# 02_-_EnergyManagementUnit.net
KiCad netlist of a schematic drawn in Altium Designer
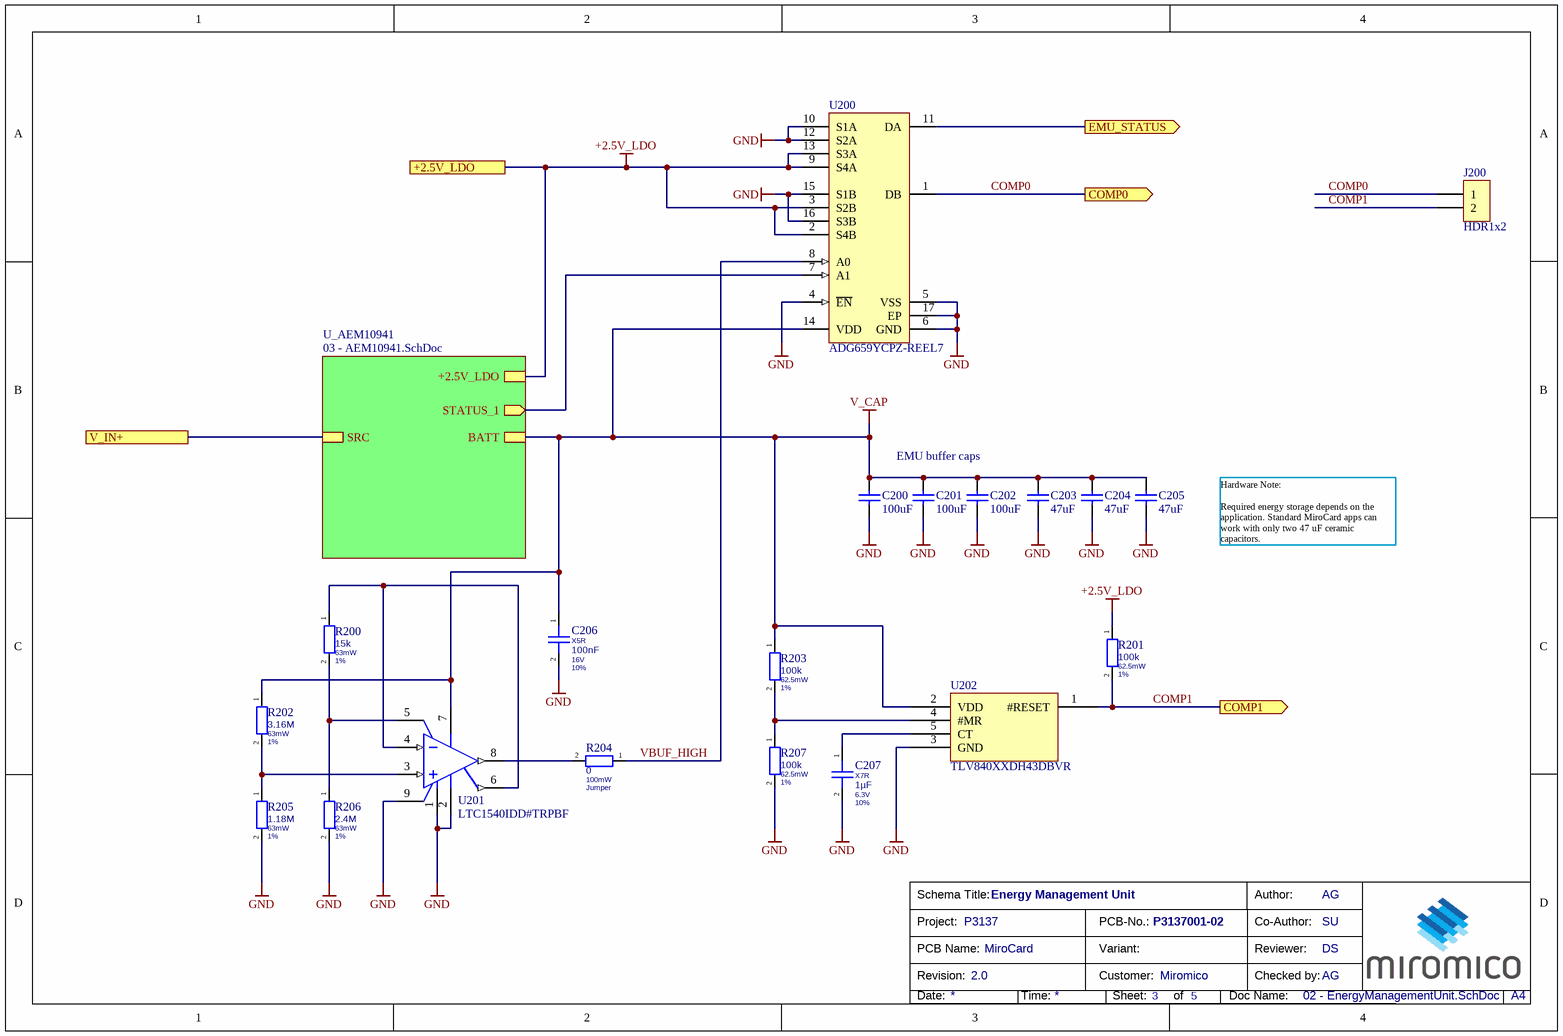
[diagram p0: 02 - EnergyManagementUnit.SchDoc]

(export (version "E")
  (design (tool "Eeschema 10.0.6"))
  (components
    (comp (ref "C200")
      (value "100uF")
      (footprint "CAPC1206(3216)145_N")
      (description "CAP 100uF 10V ±20% 1206 (3216 Metric) Thickness 1.45mm SMD")
      (fields (field (name "TOLERANCE") "Â±20%") (field (name "Comment") "CAP 100uF 10V 1206(3216)"))
      (libsource (lib "TransientBLE") (part "CMP-LMK316BBJ107ML-T"))
    )
    (comp (ref "C201")
      (value "100uF")
      (footprint "CAPC1206(3216)145_N")
      (description "CAP 100uF 10V ±20% 1206 (3216 Metric) Thickness 1.45mm SMD")
      (fields (field (name "TOLERANCE") "Â±20%") (field (name "Comment") "CAP 100uF 10V 1206(3216)"))
      (libsource (lib "TransientBLE") (part "CMP-LMK316BBJ107ML-T"))
    )
    (comp (ref "C202")
      (value "100uF")
      (footprint "CAPC1206(3216)145_N")
      (description "CAP 100uF 10V ±20% 1206 (3216 Metric) Thickness 1.45mm SMD")
      (fields (field (name "TOLERANCE") "Â±20%") (field (name "Comment") "CAP 100uF 10V 1206(3216)"))
      (libsource (lib "TransientBLE") (part "CMP-LMK316BBJ107ML-T"))
    )
    (comp (ref "C203")
      (value "47uF")
      (footprint "CAPC0805(2012)95_L")
      (description "CAP 47uF 6.3V ±20% 0805 (2012 Metric) Thickness 0.95mm SMD")
      (fields (field (name "TOLERANCE") "Â±20%") (field (name "Comment") "CAP 47uF 6.3V 0805(2012)"))
      (libsource (lib "TransientBLE") (part "CMP-GRM219R60J476ME44D"))
    )
    (comp (ref "C204")
      (value "47uF")
      (footprint "CAPC0805(2012)95_L")
      (description "CAP 47uF 6.3V ±20% 0805 (2012 Metric) Thickness 0.95mm SMD")
      (fields (field (name "TOLERANCE") "Â±20%") (field (name "Comment") "CAP 47uF 6.3V 0805(2012)"))
      (libsource (lib "TransientBLE") (part "CMP-GRM219R60J476ME44D"))
    )
    (comp (ref "C205")
      (value "47uF")
      (footprint "CAPC0805(2012)95_L")
      (description "CAP 47uF 6.3V ±20% 0805 (2012 Metric) Thickness 0.95mm SMD")
      (fields (field (name "TOLERANCE") "Â±20%") (field (name "Comment") "CAP 47uF 6.3V 0805(2012)"))
      (libsource (lib "TransientBLE") (part "CMP-GRM219R60J476ME44D"))
    )
    (comp (ref "C206")
      (value "GRM155R61C104KA88D")
      (footprint "CAPC0402(1005)60_L")
      (description "0.1µF ±10% 16V Ceramic Capacitor X5R 0402 (1005 Metric)")
      (fields
        (field (name "DIELECTRIC") "X5R")
        (field (name "CAPACITANCE") "100nF")
        (field (name "VOLTAGE RATING") "16V")
        (field (name "TOLERANCE") "10%")
        (field (name "MANUFACTURER") "Murata Electronics")
        (field (name "VOLTAGE") "16V")
      )
      (libsource (lib "Altium Vault Miromico") (part "=Capacitance"))
    )
    (comp (ref "C207")
      (value "GRM155R70J105KA12J")
      (footprint "CAPC0402(1005)60_L")
      (description "1µF ±10% 6.3V Ceramic Capacitor X7R 0402 (1005 Metric)")
      (fields
        (field (name "DIELECTRIC") "X7R")
        (field (name "CAPACITANCE") "1µF")
        (field (name "VOLTAGE RATING") "6.3V")
        (field (name "TOLERANCE") "10%")
        (field (name "MANUFACTURER") "Murata Electronics")
      )
      (libsource (lib "Altium Vault Miromico") (part "=Capacitance"))
    )
    (comp (ref "J200")
      (value "HDR1x2")
      (footprint "HDR1x2")
      (description "1x2 Pin Header, 2.54mm")
      (libsource (lib "Altium Vault Miromico") (part "HDR1x2"))
    )
    (comp (ref "R200")
      (value "PFR05S-153-FNH")
      (footprint "RESC0402(1005)_L")
      (description "15 kOhms ±1% 0.063W, 1/16W Chip Resistor 0402 (1005 Metric)  Thick Film")
      (fields
        (field (name "RESISTANCE") "15k")
        (field (name "POWER RATING") "63mW")
        (field (name "TOLERANCE") "1%")
        (field (name "MANUFACTURER") "Delta Electronics/Cyntec")
      )
      (libsource (lib "Altium Vault Miromico") (part "=Resistance"))
    )
    (comp (ref "R201")
      (value "RMCF0402FT100K")
      (footprint "RESC0402(1005)_L")
      (fields
        (field (name "RESISTANCE") "100k")
        (field (name "POWER RATING") "62.5mW")
        (field (name "TOLERANCE") "1%")
        (field (name "MANUFACTURER") "Stackpole Electronics Inc")
      )
      (libsource (lib "Altium Vault Miromico") (part "=Resistance"))
    )
    (comp (ref "R202")
      (value "CRCW04023M16FKED")
      (footprint "RESC0402(1005)_L")
      (description "3.16 MOhms ±1% 0.063W, 1/16W Chip Resistor 0402 (1005 Metric) Automotive AEC-Q200 Thick Film")
      (fields
        (field (name "RESISTANCE") "3.16M")
        (field (name "POWER RATING") "63mW")
        (field (name "TOLERANCE") "1%")
        (field (name "MANUFACTURER") "Vishay Dale")
      )
      (libsource (lib "Altium Vault Miromico") (part "=Resistance"))
    )
    (comp (ref "R203")
      (value "RMCF0402FT100K")
      (footprint "RESC0402(1005)_L")
      (fields
        (field (name "RESISTANCE") "100k")
        (field (name "POWER RATING") "62.5mW")
        (field (name "TOLERANCE") "1%")
        (field (name "MANUFACTURER") "Stackpole Electronics Inc")
      )
      (libsource (lib "Altium Vault Miromico") (part "=Resistance"))
    )
    (comp (ref "R204")
      (value "RMCF0603ZT0R00")
      (footprint "RESC0603(1608)_L")
      (description "0 Ohms Jumper 0.1W, 1/10W Chip Resistor 0603 (1608 Metric) Automotive AEC-Q200 Thick Film")
      (fields
        (field (name "RESISTANCE") "0")
        (field (name "POWER RATING") "100mW")
        (field (name "TOLERANCE") "Jumper")
        (field (name "MANUFACTURER") "Stackpole Electronics Inc")
      )
      (libsource (lib "") (part "=Resistance_1"))
    )
    (comp (ref "R205")
      (value "RMCF0402FT1M18")
      (footprint "RESC0402(1005)_L")
      (description "1.18 MOhms ±1% 0.063W, 1/16W Chip Resistor 0402 (1005 Metric) Automotive AEC-Q200 Thick Film")
      (fields
        (field (name "RESISTANCE") "1.18M")
        (field (name "POWER RATING") "63mW")
        (field (name "TOLERANCE") "1%")
        (field (name "MANUFACTURER") "Stackpole Electronics Inc")
      )
      (libsource (lib "Altium Vault Miromico") (part "=Resistance"))
    )
    (comp (ref "R206")
      (value "RMCF0402FT2M40")
      (footprint "RESC0402(1005)_L")
      (description "2.4 MOhms ±1% 0.063W, 1/16W Chip Resistor 0402 (1005 Metric) Automotive AEC-Q200 Thick Film")
      (fields
        (field (name "RESISTANCE") "2.4M")
        (field (name "POWER RATING") "63mW")
        (field (name "TOLERANCE") "1%")
        (field (name "MANUFACTURER") "Stackpole Electronics Inc")
      )
      (libsource (lib "Altium Vault Miromico") (part "=Resistance"))
    )
    (comp (ref "R207")
      (value "RMCF0402FT100K")
      (footprint "RESC0402(1005)_L")
      (fields
        (field (name "RESISTANCE") "100k")
        (field (name "POWER RATING") "62.5mW")
        (field (name "TOLERANCE") "1%")
        (field (name "MANUFACTURER") "Stackpole Electronics Inc")
      )
      (libsource (lib "Altium Vault Miromico") (part "=Resistance"))
    )
    (comp (ref "U200")
      (value "ADG659YCPZ-REEL7")
      (footprint "CP-16-4_L")
      (description "3 V / 5 V / +/-5 V CMOS 4-Channel Analog Multiplexer, -40 to 85 degC, 16-pin QFN (CP-16-4), Reel")
      (fields (field (name "MANUFACTURER") "Analog Devices"))
      (libsource (lib "Altium Content Vault") (part "ADI-ADG659-CP-16-4"))
    )
    (comp (ref "U201")
      (value "LTC1540IDD#TRPBF")
      (footprint "LT-DD8_V")
      (fields
        (field (name "MANUFACTURER") "Linear Technology")
        (field (name "GENERIC PART NUMBER") "LTC1540")
      )
      (libsource (lib "Altium Content Vault") (part "LT-LTC1540-DFN8"))
    )
    (comp (ref "U202")
      (value "TLV840XXDH43DBVR")
      (footprint "SOT23-5 SOT-23-5")
      (description "Low-voltage supervisor with adjustable-reset time delay and manual reset")
      (fields (field (name "MANUFACTURER") "Texas Instruments"))
      (libsource (lib "Altium Vault Miromico") (part "TLV840XXDH43DBVR"))
    )
  )
  (nets
    (net (code "1") (name "+2.5V_LDO") (class "Default")
      (node (ref "R201") (pin "1") (pinfunction "1_1") (pintype "passive"))
      (node (ref "U200") (pin "13") (pinfunction "S3A_13") (pintype "passive"))
      (node (ref "U200") (pin "2") (pinfunction "S4B_2") (pintype "passive"))
      (node (ref "U200") (pin "3") (pinfunction "S2B_3") (pintype "passive"))
      (node (ref "U200") (pin "9") (pinfunction "S4A_9") (pintype "passive"))
    )
    (net (code "2") (name "/COMP0") (class "Default")
      (node (ref "J200") (pin "1") (pinfunction "1_1") (pintype "passive"))
      (node (ref "U200") (pin "1") (pinfunction "DB_1") (pintype "passive"))
    )
    (net (code "3") (name "/COMP1") (class "Default")
      (node (ref "J200") (pin "2") (pinfunction "2_2") (pintype "passive"))
      (node (ref "R201") (pin "2") (pinfunction "2_2") (pintype "passive"))
      (node (ref "U202") (pin "1") (pinfunction "#RESET_1") (pintype "passive"))
    )
    (net (code "4") (name "/EMU_STATUS") (class "Default")
      (node (ref "U200") (pin "11") (pinfunction "DA_11") (pintype "passive"))
    )
    (net (code "5") (name "/STATUS_1") (class "Default")
      (node (ref "U200") (pin "7") (pinfunction "A1_7") (pintype "input"))
    )
    (net (code "6") (name "/VBUF_HIGH") (class "Default")
      (node (ref "R204") (pin "1") (pinfunction "1_1") (pintype "passive"))
      (node (ref "U200") (pin "8") (pinfunction "A0_8") (pintype "input"))
    )
    (net (code "8") (name "GND") (class "Default")
      (node (ref "C200") (pin "1") (pinfunction "1_1") (pintype "passive"))
      (node (ref "C201") (pin "1") (pinfunction "1_1") (pintype "passive"))
      (node (ref "C202") (pin "1") (pinfunction "1_1") (pintype "passive"))
      (node (ref "C203") (pin "2") (pinfunction "2_2") (pintype "passive"))
      (node (ref "C204") (pin "2") (pinfunction "2_2") (pintype "passive"))
      (node (ref "C205") (pin "2") (pinfunction "2_2") (pintype "passive"))
      (node (ref "C206") (pin "2") (pinfunction "2_2") (pintype "passive"))
      (node (ref "C207") (pin "2") (pinfunction "2_2") (pintype "passive"))
      (node (ref "R205") (pin "2") (pinfunction "2_2") (pintype "passive"))
      (node (ref "R206") (pin "2") (pinfunction "2_2") (pintype "passive"))
      (node (ref "R207") (pin "2") (pinfunction "2_2") (pintype "passive"))
      (node (ref "U200") (pin "10") (pinfunction "S1A_10") (pintype "passive"))
      (node (ref "U200") (pin "12") (pinfunction "S2A_12") (pintype "passive"))
      (node (ref "U200") (pin "15") (pinfunction "S1B_15") (pintype "passive"))
      (node (ref "U200") (pin "16") (pinfunction "S3B_16") (pintype "passive"))
      (node (ref "U200") (pin "17") (pinfunction "EP_17") (pintype "passive"))
      (node (ref "U200") (pin "4") (pinfunction "~{EN}_4") (pintype "input"))
      (node (ref "U200") (pin "5") (pinfunction "VSS_5") (pintype "power_in"))
      (node (ref "U200") (pin "6") (pinfunction "GND_6") (pintype "power_in"))
      (node (ref "U201") (pin "1") (pinfunction "GND_1") (pintype "power_in"))
      (node (ref "U201") (pin "2") (pinfunction "V-_2") (pintype "power_in"))
      (node (ref "U201") (pin "9") (pinfunction "EP_9") (pintype "power_in"))
      (node (ref "U202") (pin "3") (pinfunction "GND_3") (pintype "power_in"))
    )
    (net (code "9") (name "Net-(U201-HYST)") (class "Default")
      (node (ref "R200") (pin "2") (pinfunction "2_2") (pintype "passive"))
      (node (ref "R206") (pin "1") (pinfunction "1_1") (pintype "passive"))
      (node (ref "U201") (pin "5") (pinfunction "HYST_5") (pintype "passive"))
    )
    (net (code "10") (name "Net-(U201-IN+)") (class "Default")
      (node (ref "R202") (pin "2") (pinfunction "2_2") (pintype "passive"))
      (node (ref "R205") (pin "1") (pinfunction "1_1") (pintype "passive"))
      (node (ref "U201") (pin "3") (pinfunction "IN+_3") (pintype "input"))
    )
    (net (code "11") (name "Net-(U201-IN-)") (class "Default")
      (node (ref "R200") (pin "1") (pinfunction "1_1") (pintype "passive"))
      (node (ref "U201") (pin "4") (pinfunction "IN-_4") (pintype "input"))
      (node (ref "U201") (pin "6") (pinfunction "REF_6") (pintype "output"))
    )
    (net (code "12") (name "Net-(U201-OUT)") (class "Default")
      (node (ref "R204") (pin "2") (pinfunction "2_2") (pintype "passive"))
      (node (ref "U201") (pin "8") (pinfunction "OUT_8") (pintype "output"))
    )
    (net (code "13") (name "Net-(U202-#MR)") (class "Default")
      (node (ref "R203") (pin "2") (pinfunction "2_2") (pintype "passive"))
      (node (ref "R207") (pin "1") (pinfunction "1_1") (pintype "passive"))
      (node (ref "U202") (pin "4") (pinfunction "#MR_4") (pintype "passive"))
    )
    (net (code "14") (name "Net-(U202-CT)") (class "Default")
      (node (ref "C207") (pin "1") (pinfunction "1_1") (pintype "passive"))
      (node (ref "U202") (pin "5") (pinfunction "CT_5") (pintype "passive"))
    )
    (net (code "15") (name "V_CAP") (class "Default")
      (node (ref "C200") (pin "2") (pinfunction "2_2") (pintype "passive"))
      (node (ref "C201") (pin "2") (pinfunction "2_2") (pintype "passive"))
      (node (ref "C202") (pin "2") (pinfunction "2_2") (pintype "passive"))
      (node (ref "C203") (pin "1") (pinfunction "1_1") (pintype "passive"))
      (node (ref "C204") (pin "1") (pinfunction "1_1") (pintype "passive"))
      (node (ref "C205") (pin "1") (pinfunction "1_1") (pintype "passive"))
      (node (ref "C206") (pin "1") (pinfunction "1_1") (pintype "passive"))
      (node (ref "R202") (pin "1") (pinfunction "1_1") (pintype "passive"))
      (node (ref "R203") (pin "1") (pinfunction "1_1") (pintype "passive"))
      (node (ref "U200") (pin "14") (pinfunction "VDD_14") (pintype "power_in"))
      (node (ref "U201") (pin "7") (pinfunction "V+_7") (pintype "power_in"))
      (node (ref "U202") (pin "2") (pinfunction "VDD_2") (pintype "power_in"))
    )
  )
)
